# ProPrj_ExternalProgrammer.net
KiCad netlist of a schematic drawn in EasyEDA Pro
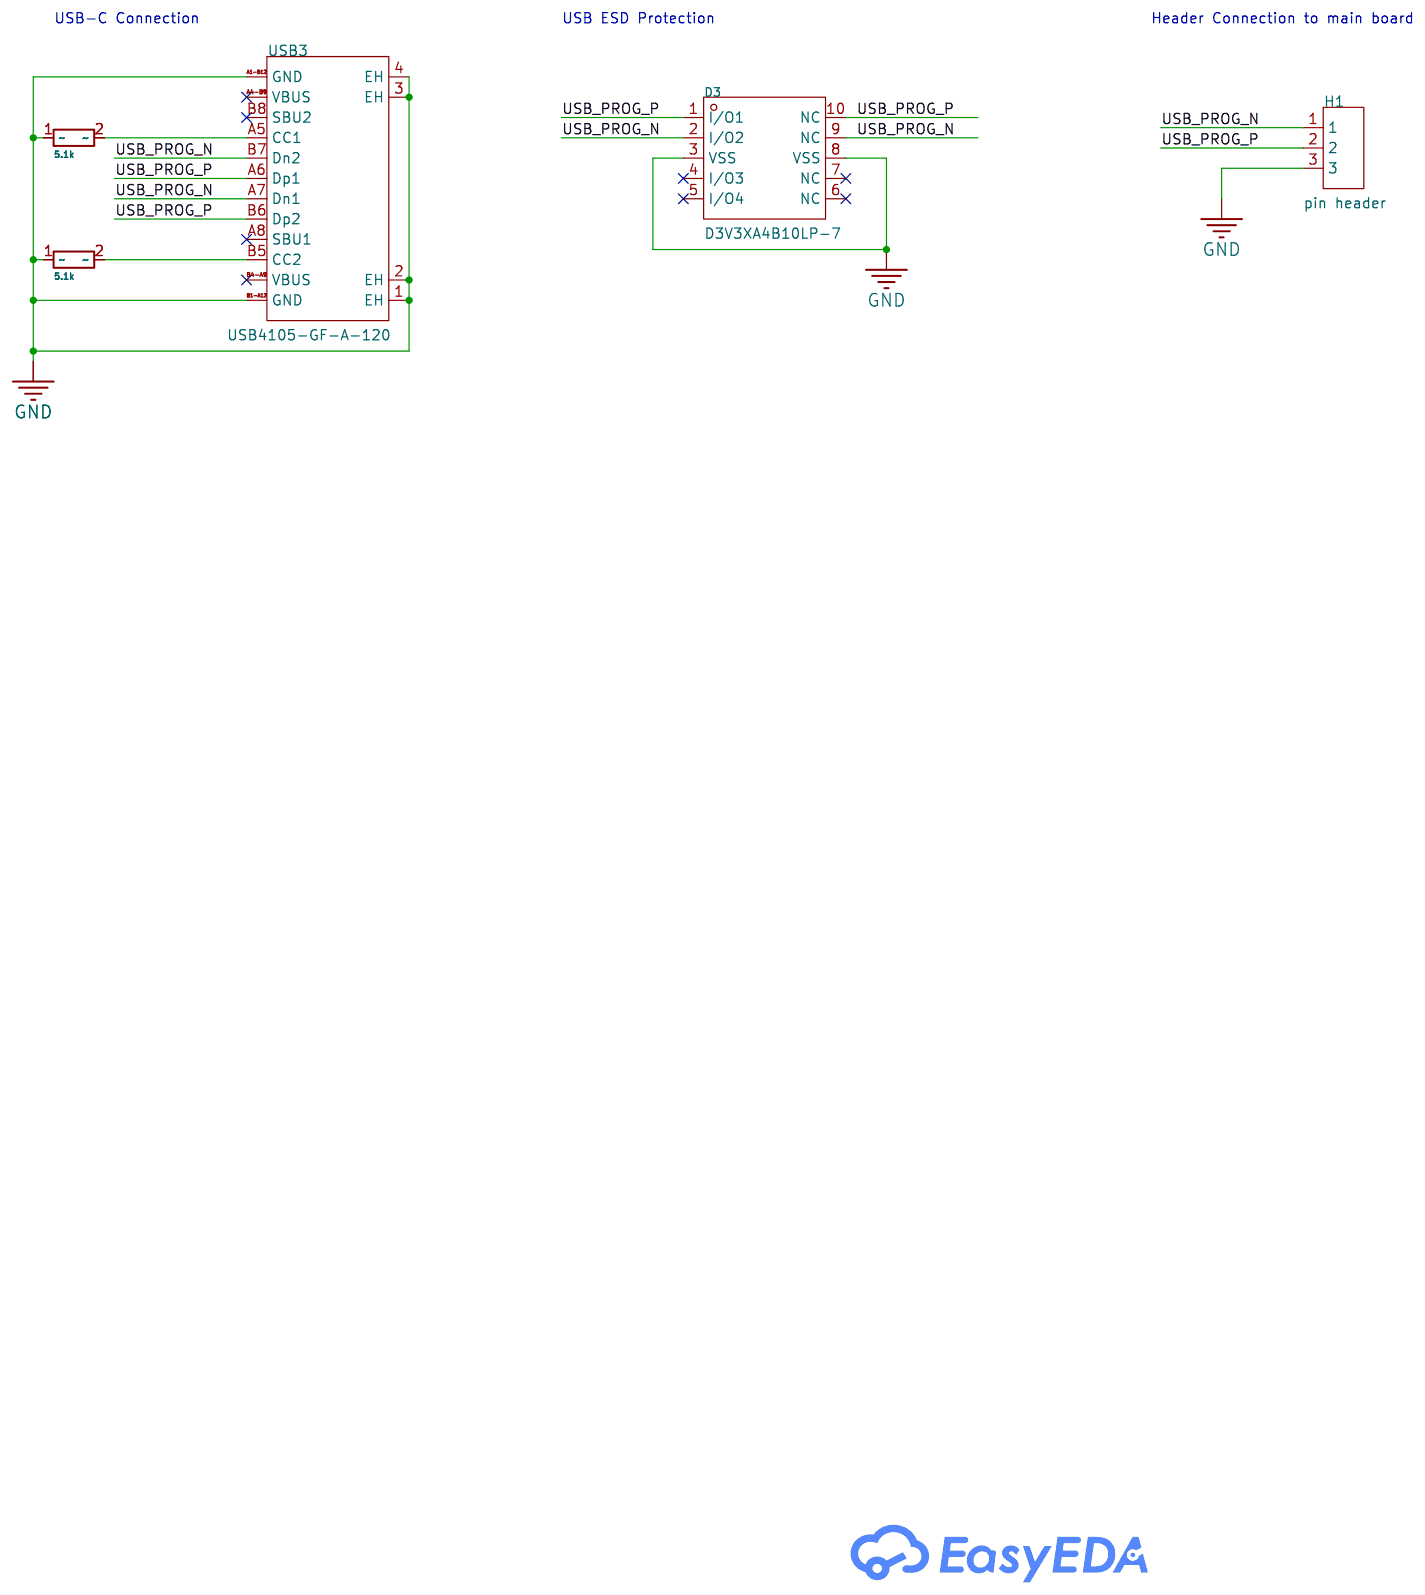
[diagram p0: schematic sheet]

(export (version "E")
  (design (tool "Eeschema 10.0.6"))
  (components
    (comp (ref "D3")
      (value "D3V3XA4B10LP-7")
      (footprint "easyedapro:U-DFN2510-10_L2.5-W1.0-P0.50-BL")
      (fields (field (name "Manufacturer") "DIODES(美台)"))
      (libsource (lib "easyedapro") (part "D3V3XA4B10LP-7"))
    )
    (comp (ref "H1")
      (value "pin header")
      (footprint "easyedapro:HDR-TH_3P-P2.54-V-M-1")
      (fields (field (name "Manufacturer") "hanxia(韩下)"))
      (libsource (lib "easyedapro") (part "HX PH254-01-03-Z-L11.5 PCB PIN HEADER"))
    )
    (comp (ref "R38")
      (value "5.1k")
      (footprint "easyedapro:Resistor_SMD:R_0805_2012Metric")
      (libsource (lib "easyedapro") (part "Device_R"))
    )
    (comp (ref "R40")
      (value "5.1k")
      (footprint "easyedapro:Resistor_SMD:R_0805_2012Metric")
      (libsource (lib "easyedapro") (part "Device_R"))
    )
    (comp (ref "USB3")
      (value "USB4105-GF-A-120")
      (footprint "easyedapro:USB-C-SMD_MC-311D")
      (fields (field (name "Manufacturer") "GCT"))
      (libsource (lib "easyedapro") (part "USB4105-GF-A-120"))
    )
  )
  (nets
    (net (code "1") (name "/USB_PROG_N") (class "Default")
      (node (ref "D3") (pin "2") (pinfunction "I/O2_2") (pintype "input"))
      (node (ref "D3") (pin "9") (pinfunction "NC_9") (pintype "input"))
      (node (ref "H1") (pin "1") (pinfunction "1_1") (pintype "unspecified"))
      (node (ref "USB3") (pin "A7") (pinfunction "Dn1_A7") (pintype "unspecified"))
      (node (ref "USB3") (pin "B7") (pinfunction "Dn2_B7") (pintype "unspecified"))
    )
    (net (code "2") (name "/USB_PROG_P") (class "Default")
      (node (ref "D3") (pin "1") (pinfunction "I/O1_1") (pintype "input"))
      (node (ref "D3") (pin "10") (pinfunction "NC_10") (pintype "input"))
      (node (ref "H1") (pin "2") (pinfunction "2_2") (pintype "unspecified"))
      (node (ref "USB3") (pin "A6") (pinfunction "Dp1_A6") (pintype "unspecified"))
      (node (ref "USB3") (pin "B6") (pinfunction "Dp2_B6") (pintype "unspecified"))
    )
    (net (code "3") (name "GND") (class "Default")
      (node (ref "D3") (pin "3") (pinfunction "VSS_3") (pintype "input"))
      (node (ref "D3") (pin "8") (pinfunction "VSS_8") (pintype "input"))
      (node (ref "H1") (pin "3") (pinfunction "3_3") (pintype "unspecified"))
      (node (ref "R38") (pin "1") (pinfunction "~_1") (pintype "unspecified"))
      (node (ref "R40") (pin "1") (pinfunction "~_1") (pintype "unspecified"))
      (node (ref "USB3") (pin "1") (pinfunction "EH_1") (pintype "unspecified"))
      (node (ref "USB3") (pin "2") (pinfunction "EH_2") (pintype "unspecified"))
      (node (ref "USB3") (pin "3") (pinfunction "EH_3") (pintype "unspecified"))
      (node (ref "USB3") (pin "4") (pinfunction "EH_4") (pintype "unspecified"))
      (node (ref "USB3") (pin "A1-B12") (pinfunction "GND_A1-B12") (pintype "unspecified"))
      (node (ref "USB3") (pin "B1-A12") (pinfunction "GND_B1-A12") (pintype "unspecified"))
    )
    (net (code "4") (name "Net-(USB3-CC1)") (class "Default")
      (node (ref "R40") (pin "2") (pinfunction "~_2") (pintype "unspecified"))
      (node (ref "USB3") (pin "A5") (pinfunction "CC1_A5") (pintype "unspecified"))
    )
    (net (code "5") (name "Net-(USB3-CC2)") (class "Default")
      (node (ref "R38") (pin "2") (pinfunction "~_2") (pintype "unspecified"))
      (node (ref "USB3") (pin "B5") (pinfunction "CC2_B5") (pintype "unspecified"))
    )
    (net (code "6") (name "unconnected-(D3-I{slash}O3-Pad4)") (class "Default")
      (node (ref "D3") (pin "4") (pinfunction "I/O3_4") (pintype "input+no_connect"))
    )
    (net (code "7") (name "unconnected-(D3-I{slash}O4-Pad5)") (class "Default")
      (node (ref "D3") (pin "5") (pinfunction "I/O4_5") (pintype "input+no_connect"))
    )
    (net (code "8") (name "unconnected-(D3-NC-Pad6)") (class "Default")
      (node (ref "D3") (pin "6") (pinfunction "NC_6") (pintype "input+no_connect"))
    )
    (net (code "9") (name "unconnected-(D3-NC-Pad7)") (class "Default")
      (node (ref "D3") (pin "7") (pinfunction "NC_7") (pintype "input+no_connect"))
    )
    (net (code "10") (name "unconnected-(USB3-SBU1-PadA8)") (class "Default")
      (node (ref "USB3") (pin "A8") (pinfunction "SBU1_A8") (pintype "unspecified+no_connect"))
    )
    (net (code "11") (name "unconnected-(USB3-SBU2-PadB8)") (class "Default")
      (node (ref "USB3") (pin "B8") (pinfunction "SBU2_B8") (pintype "unspecified+no_connect"))
    )
    (net (code "12") (name "unconnected-(USB3-VBUS-PadA4-B9)") (class "Default")
      (node (ref "USB3") (pin "A4-B9") (pinfunction "VBUS_A4-B9") (pintype "unspecified+no_connect"))
    )
    (net (code "13") (name "unconnected-(USB3-VBUS-PadB4-A9)") (class "Default")
      (node (ref "USB3") (pin "B4-A9") (pinfunction "VBUS_B4-A9") (pintype "unspecified+no_connect"))
    )
  )
)
